# pcb.net
KiCad netlist of a schematic drawn in EasyEDA Pro
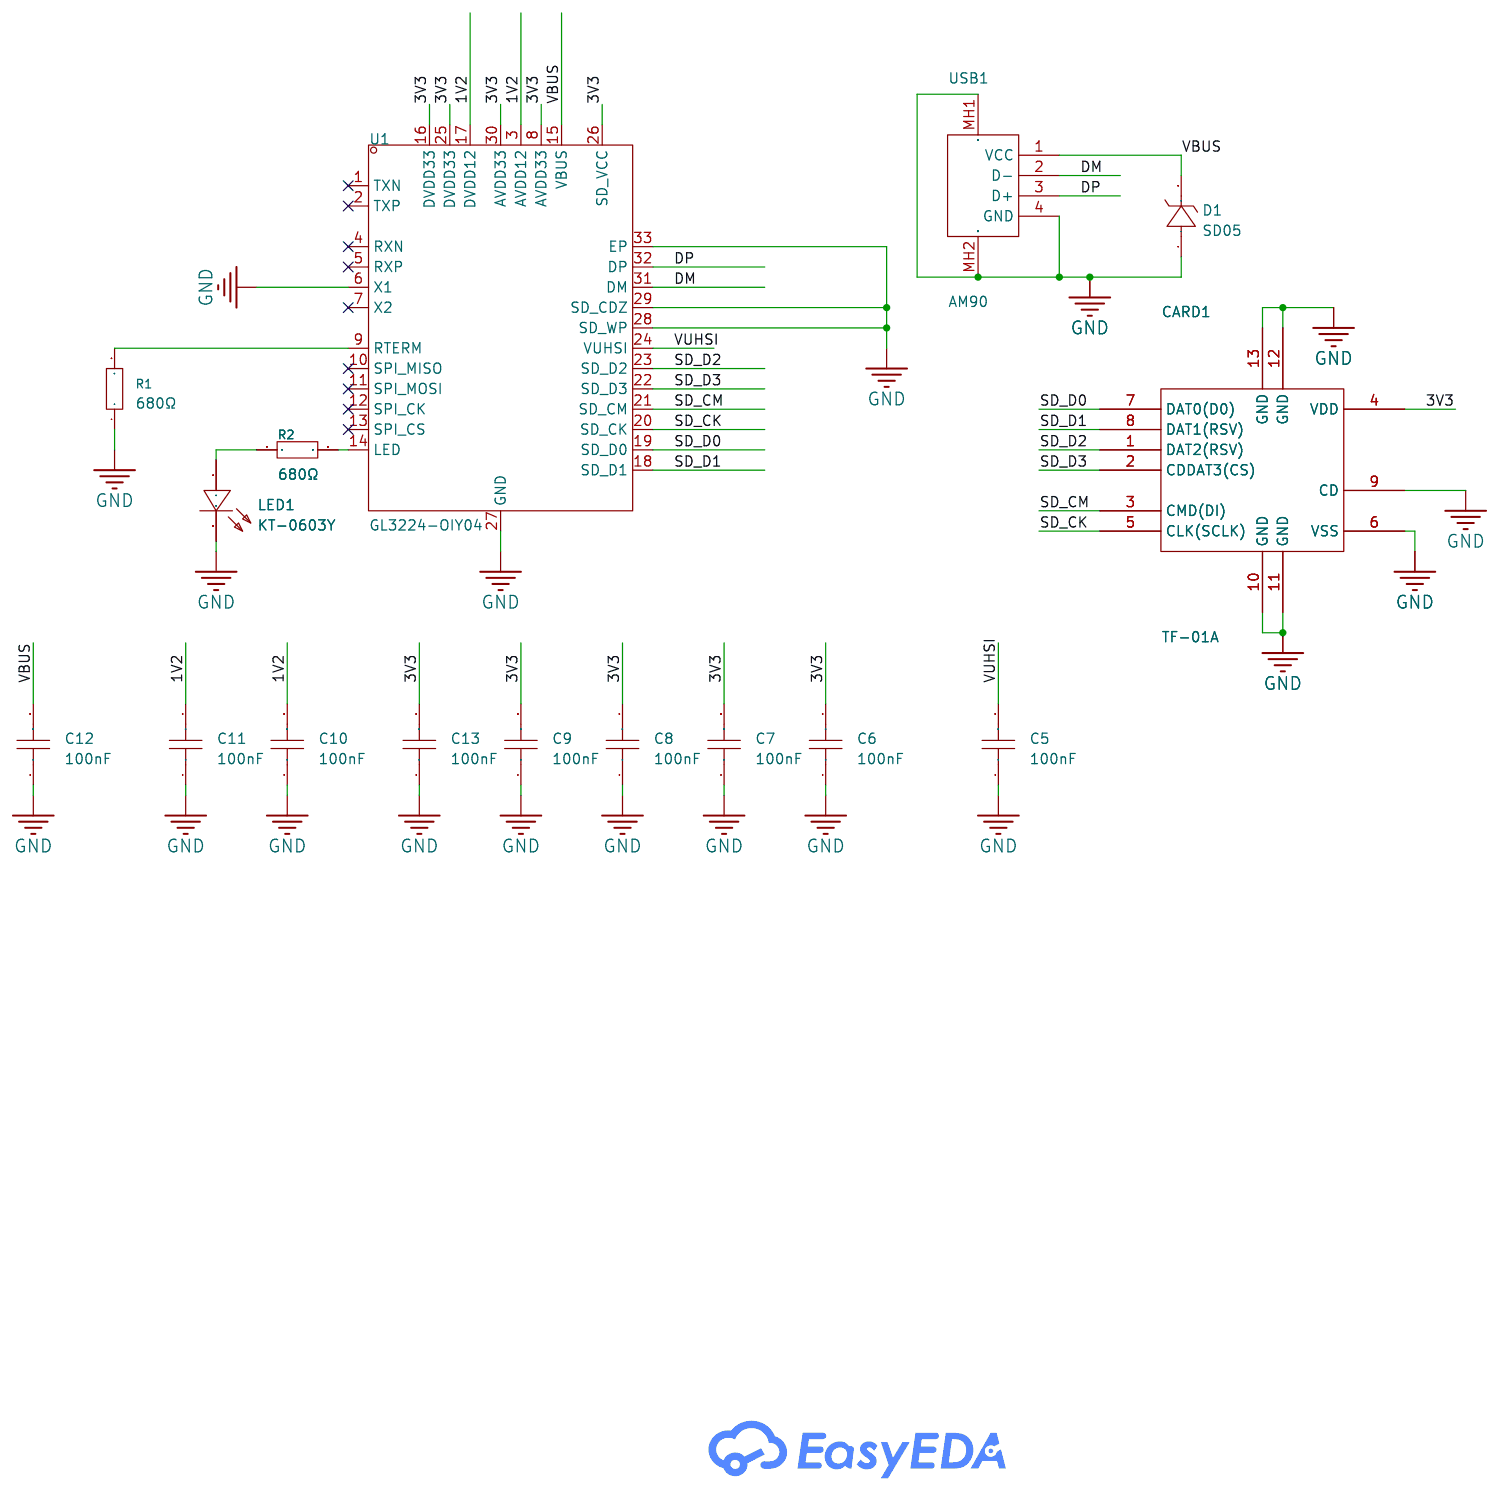
[diagram p0: schematic sheet]

(export (version "E")
  (design (tool "Eeschema 10.0.6"))
  (components
    (comp (ref "C5")
      (value "100nF")
      (footprint "easyedapro:C0402")
      (description "Capacitance:100nF Tolerance:±10% Tolerance:±10% Voltage Rating:16V Temperature Coefficient:X7R")
      (fields
        (field (name "Manufacturer Part") "CL05B104KO5NNNC")
        (field (name "Manufacturer") "SAMSUNG(三星)")
      )
      (libsource (lib "easyedapro") (part "CL05B104KO5NNNC"))
    )
    (comp (ref "C6")
      (value "100nF")
      (footprint "easyedapro:C0402")
      (description "Capacitance:100nF Tolerance:±10% Tolerance:±10% Voltage Rating:16V Temperature Coefficient:X7R")
      (fields
        (field (name "Manufacturer Part") "CL05B104KO5NNNC")
        (field (name "Manufacturer") "SAMSUNG(三星)")
      )
      (libsource (lib "easyedapro") (part "CL05B104KO5NNNC"))
    )
    (comp (ref "C7")
      (value "100nF")
      (footprint "easyedapro:C0402")
      (description "Capacitance:100nF Tolerance:±10% Tolerance:±10% Voltage Rating:16V Temperature Coefficient:X7R")
      (fields
        (field (name "Manufacturer Part") "CL05B104KO5NNNC")
        (field (name "Manufacturer") "SAMSUNG(三星)")
      )
      (libsource (lib "easyedapro") (part "CL05B104KO5NNNC"))
    )
    (comp (ref "C8")
      (value "100nF")
      (footprint "easyedapro:C0402")
      (description "Capacitance:100nF Tolerance:±10% Tolerance:±10% Voltage Rating:16V Temperature Coefficient:X7R")
      (fields
        (field (name "Manufacturer Part") "CL05B104KO5NNNC")
        (field (name "Manufacturer") "SAMSUNG(三星)")
      )
      (libsource (lib "easyedapro") (part "CL05B104KO5NNNC"))
    )
    (comp (ref "C9")
      (value "100nF")
      (footprint "easyedapro:C0402")
      (description "Capacitance:100nF Tolerance:±10% Tolerance:±10% Voltage Rating:16V Temperature Coefficient:X7R")
      (fields
        (field (name "Manufacturer Part") "CL05B104KO5NNNC")
        (field (name "Manufacturer") "SAMSUNG(三星)")
      )
      (libsource (lib "easyedapro") (part "CL05B104KO5NNNC"))
    )
    (comp (ref "C10")
      (value "100nF")
      (footprint "easyedapro:C0402")
      (description "Capacitance:100nF Tolerance:±10% Tolerance:±10% Voltage Rating:16V Temperature Coefficient:X7R")
      (fields
        (field (name "Manufacturer Part") "CL05B104KO5NNNC")
        (field (name "Manufacturer") "SAMSUNG(三星)")
      )
      (libsource (lib "easyedapro") (part "CL05B104KO5NNNC"))
    )
    (comp (ref "C11")
      (value "100nF")
      (footprint "easyedapro:C0402")
      (description "Capacitance:100nF Tolerance:±10% Tolerance:±10% Voltage Rating:16V Temperature Coefficient:X7R")
      (fields
        (field (name "Manufacturer Part") "CL05B104KO5NNNC")
        (field (name "Manufacturer") "SAMSUNG(三星)")
      )
      (libsource (lib "easyedapro") (part "CL05B104KO5NNNC"))
    )
    (comp (ref "C12")
      (value "100nF")
      (footprint "easyedapro:C0402")
      (description "Capacitance:100nF Tolerance:±10% Tolerance:±10% Voltage Rating:16V Temperature Coefficient:X7R")
      (fields
        (field (name "Manufacturer Part") "CL05B104KO5NNNC")
        (field (name "Manufacturer") "SAMSUNG(三星)")
      )
      (libsource (lib "easyedapro") (part "CL05B104KO5NNNC"))
    )
    (comp (ref "C13")
      (value "100nF")
      (footprint "easyedapro:C0402")
      (description "Capacitance:100nF Tolerance:±10% Tolerance:±10% Voltage Rating:16V Temperature Coefficient:X7R")
      (fields
        (field (name "Manufacturer Part") "CL05B104KO5NNNC")
        (field (name "Manufacturer") "SAMSUNG(三星)")
      )
      (libsource (lib "easyedapro") (part "CL05B104KO5NNNC"))
    )
    (comp (ref "CARD1")
      (value "TF-01A")
      (footprint "easyedapro:TF-SMD_TF-01A")
      (fields (field (name "Manufacturer") "韩国韩荣"))
      (libsource (lib "easyedapro") (part "TF-01A"))
    )
    (comp (ref "D1")
      (value "SD05")
      (footprint "easyedapro:SOD-323_L1.8-W1.3-LS2.5-FD")
      (fields (field (name "Manufacturer") "MDD(辰达半导体)"))
      (libsource (lib "easyedapro") (part "SD05_C502527"))
    )
    (comp (ref "LED1")
      (value "KT-0603Y")
      (footprint "easyedapro:LED0603-R-RD")
      (fields (field (name "Manufacturer") "KENTO"))
      (libsource (lib "easyedapro") (part "0603YYellow light 90-110"))
    )
    (comp (ref "R1")
      (value "680Ω")
      (footprint "easyedapro:R0603")
      (fields
        (field (name "Manufacturer Part") "0603WAF6800T5E")
        (field (name "Manufacturer") "UNI-ROYAL(厚声)")
      )
      (libsource (lib "easyedapro") (part "0603WAF6800T5E"))
    )
    (comp (ref "R2")
      (value "680Ω")
      (footprint "easyedapro:R0603")
      (fields
        (field (name "Manufacturer Part") "0603WAF6800T5E")
        (field (name "Manufacturer") "UNI-ROYAL(厚声)")
      )
      (libsource (lib "easyedapro") (part "0603WAF6800T5E"))
    )
    (comp (ref "U1")
      (value "GL3224-OIY04")
      (footprint "easyedapro:HQFN-32_L5.0-W5.0-P0.50-BL-EP3.0")
      (fields (field (name "Manufacturer") "GENESYS(创惟)"))
      (libsource (lib "easyedapro") (part "GL3224-OIY04"))
    )
    (comp (ref "USB1")
      (value "AM90")
      (footprint "easyedapro:USB-AM-TH_AM90")
      (fields (field (name "Manufacturer") "SHOU HAN(首韩)"))
      (libsource (lib "easyedapro") (part "AM90"))
    )
  )
  (nets
    (net (code "1") (name "/1V2") (class "Default")
      (node (ref "C10") (pin "2") (pinfunction "2_2") (pintype "unspecified"))
      (node (ref "C11") (pin "2") (pinfunction "2_2") (pintype "unspecified"))
      (node (ref "U1") (pin "17") (pinfunction "DVDD12_17") (pintype "unspecified"))
      (node (ref "U1") (pin "3") (pinfunction "AVDD12_3") (pintype "unspecified"))
    )
    (net (code "2") (name "/3V3") (class "Default")
      (node (ref "C13") (pin "2") (pinfunction "2_2") (pintype "unspecified"))
      (node (ref "C6") (pin "2") (pinfunction "2_2") (pintype "unspecified"))
      (node (ref "C7") (pin "2") (pinfunction "2_2") (pintype "unspecified"))
      (node (ref "C8") (pin "2") (pinfunction "2_2") (pintype "unspecified"))
      (node (ref "C9") (pin "2") (pinfunction "2_2") (pintype "unspecified"))
      (node (ref "CARD1") (pin "4") (pinfunction "VDD_4") (pintype "input"))
      (node (ref "U1") (pin "16") (pinfunction "DVDD33_16") (pintype "unspecified"))
      (node (ref "U1") (pin "25") (pinfunction "DVDD33_25") (pintype "unspecified"))
      (node (ref "U1") (pin "26") (pinfunction "SD_VCC_26") (pintype "unspecified"))
      (node (ref "U1") (pin "30") (pinfunction "AVDD33_30") (pintype "unspecified"))
      (node (ref "U1") (pin "8") (pinfunction "AVDD33_8") (pintype "unspecified"))
    )
    (net (code "3") (name "/DM") (class "Default")
      (node (ref "U1") (pin "31") (pinfunction "DM_31") (pintype "unspecified"))
      (node (ref "USB1") (pin "2") (pinfunction "D-_2") (pintype "input"))
    )
    (net (code "4") (name "/DP") (class "Default")
      (node (ref "U1") (pin "32") (pinfunction "DP_32") (pintype "unspecified"))
      (node (ref "USB1") (pin "3") (pinfunction "D+_3") (pintype "input"))
    )
    (net (code "5") (name "/SD_CK") (class "Default")
      (node (ref "CARD1") (pin "5") (pinfunction "CLK(SCLK)_5") (pintype "input"))
      (node (ref "U1") (pin "20") (pinfunction "SD_CK_20") (pintype "unspecified"))
    )
    (net (code "6") (name "/SD_CM") (class "Default")
      (node (ref "CARD1") (pin "3") (pinfunction "CMD(DI)_3") (pintype "input"))
      (node (ref "U1") (pin "21") (pinfunction "SD_CM_21") (pintype "unspecified"))
    )
    (net (code "7") (name "/SD_D0") (class "Default")
      (node (ref "CARD1") (pin "7") (pinfunction "DAT0(D0)_7") (pintype "bidirectional"))
      (node (ref "U1") (pin "19") (pinfunction "SD_D0_19") (pintype "unspecified"))
    )
    (net (code "8") (name "/SD_D1") (class "Default")
      (node (ref "CARD1") (pin "8") (pinfunction "DAT1(RSV)_8") (pintype "bidirectional"))
      (node (ref "U1") (pin "18") (pinfunction "SD_D1_18") (pintype "unspecified"))
    )
    (net (code "9") (name "/SD_D2") (class "Default")
      (node (ref "CARD1") (pin "1") (pinfunction "DAT2(RSV)_1") (pintype "bidirectional"))
      (node (ref "U1") (pin "23") (pinfunction "SD_D2_23") (pintype "unspecified"))
    )
    (net (code "10") (name "/SD_D3") (class "Default")
      (node (ref "CARD1") (pin "2") (pinfunction "CDDAT3(CS)_2") (pintype "bidirectional"))
      (node (ref "U1") (pin "22") (pinfunction "SD_D3_22") (pintype "unspecified"))
    )
    (net (code "11") (name "/VBUS") (class "Default")
      (node (ref "C12") (pin "2") (pinfunction "2_2") (pintype "unspecified"))
      (node (ref "D1") (pin "2") (pinfunction "K_2") (pintype "unspecified"))
      (node (ref "U1") (pin "15") (pinfunction "VBUS_15") (pintype "unspecified"))
      (node (ref "USB1") (pin "1") (pinfunction "VCC_1") (pintype "input"))
    )
    (net (code "12") (name "/VUHSI") (class "Default")
      (node (ref "C5") (pin "2") (pinfunction "2_2") (pintype "unspecified"))
      (node (ref "U1") (pin "24") (pinfunction "VUHSI_24") (pintype "unspecified"))
    )
    (net (code "13") (name "GND") (class "Default")
      (node (ref "C10") (pin "1") (pinfunction "1_1") (pintype "unspecified"))
      (node (ref "C11") (pin "1") (pinfunction "1_1") (pintype "unspecified"))
      (node (ref "C12") (pin "1") (pinfunction "1_1") (pintype "unspecified"))
      (node (ref "C13") (pin "1") (pinfunction "1_1") (pintype "unspecified"))
      (node (ref "C5") (pin "1") (pinfunction "1_1") (pintype "unspecified"))
      (node (ref "C6") (pin "1") (pinfunction "1_1") (pintype "unspecified"))
      (node (ref "C7") (pin "1") (pinfunction "1_1") (pintype "unspecified"))
      (node (ref "C8") (pin "1") (pinfunction "1_1") (pintype "unspecified"))
      (node (ref "C9") (pin "1") (pinfunction "1_1") (pintype "unspecified"))
      (node (ref "CARD1") (pin "10") (pinfunction "GND_10") (pintype "input"))
      (node (ref "CARD1") (pin "11") (pinfunction "GND_11") (pintype "input"))
      (node (ref "CARD1") (pin "12") (pinfunction "GND_12") (pintype "input"))
      (node (ref "CARD1") (pin "13") (pinfunction "GND_13") (pintype "input"))
      (node (ref "CARD1") (pin "6") (pinfunction "VSS_6") (pintype "input"))
      (node (ref "CARD1") (pin "9") (pinfunction "CD_9") (pintype "input"))
      (node (ref "D1") (pin "1") (pinfunction "A_1") (pintype "unspecified"))
      (node (ref "LED1") (pin "2") (pinfunction "K_2") (pintype "unspecified"))
      (node (ref "R1") (pin "1") (pinfunction "1_1") (pintype "input"))
      (node (ref "U1") (pin "27") (pinfunction "GND_27") (pintype "unspecified"))
      (node (ref "U1") (pin "28") (pinfunction "SD_WP_28") (pintype "unspecified"))
      (node (ref "U1") (pin "29") (pinfunction "SD_CDZ_29") (pintype "unspecified"))
      (node (ref "U1") (pin "33") (pinfunction "EP_33") (pintype "unspecified"))
      (node (ref "U1") (pin "6") (pinfunction "X1_6") (pintype "unspecified"))
      (node (ref "USB1") (pin "4") (pinfunction "GND_4") (pintype "input"))
      (node (ref "USB1") (pin "MH1") (pinfunction "MH1_MH1") (pintype "unspecified"))
      (node (ref "USB1") (pin "MH2") (pinfunction "MH2_MH2") (pintype "unspecified"))
    )
    (net (code "14") (name "Net-(LED1-A)") (class "Default")
      (node (ref "LED1") (pin "1") (pinfunction "A_1") (pintype "unspecified"))
      (node (ref "R2") (pin "1") (pinfunction "1_1") (pintype "input"))
    )
    (net (code "15") (name "Net-(U1-LED)") (class "Default")
      (node (ref "R2") (pin "2") (pinfunction "2_2") (pintype "input"))
      (node (ref "U1") (pin "14") (pinfunction "LED_14") (pintype "unspecified"))
    )
    (net (code "16") (name "Net-(U1-RTERM)") (class "Default")
      (node (ref "R1") (pin "2") (pinfunction "2_2") (pintype "input"))
      (node (ref "U1") (pin "9") (pinfunction "RTERM_9") (pintype "unspecified"))
    )
    (net (code "17") (name "unconnected-(U1-RXN-Pad4)") (class "Default")
      (node (ref "U1") (pin "4") (pinfunction "RXN_4") (pintype "unspecified+no_connect"))
    )
    (net (code "18") (name "unconnected-(U1-RXP-Pad5)") (class "Default")
      (node (ref "U1") (pin "5") (pinfunction "RXP_5") (pintype "unspecified+no_connect"))
    )
    (net (code "19") (name "unconnected-(U1-SPI_CK-Pad12)") (class "Default")
      (node (ref "U1") (pin "12") (pinfunction "SPI_CK_12") (pintype "unspecified+no_connect"))
    )
    (net (code "20") (name "unconnected-(U1-SPI_CS-Pad13)") (class "Default")
      (node (ref "U1") (pin "13") (pinfunction "SPI_CS_13") (pintype "unspecified+no_connect"))
    )
    (net (code "21") (name "unconnected-(U1-SPI_MISO-Pad10)") (class "Default")
      (node (ref "U1") (pin "10") (pinfunction "SPI_MISO_10") (pintype "unspecified+no_connect"))
    )
    (net (code "22") (name "unconnected-(U1-SPI_MOSI-Pad11)") (class "Default")
      (node (ref "U1") (pin "11") (pinfunction "SPI_MOSI_11") (pintype "unspecified+no_connect"))
    )
    (net (code "23") (name "unconnected-(U1-TXN-Pad1)") (class "Default")
      (node (ref "U1") (pin "1") (pinfunction "TXN_1") (pintype "unspecified+no_connect"))
    )
    (net (code "24") (name "unconnected-(U1-TXP-Pad2)") (class "Default")
      (node (ref "U1") (pin "2") (pinfunction "TXP_2") (pintype "unspecified+no_connect"))
    )
    (net (code "25") (name "unconnected-(U1-X2-Pad7)") (class "Default")
      (node (ref "U1") (pin "7") (pinfunction "X2_7") (pintype "unspecified+no_connect"))
    )
  )
)
